# Block.net
KiCad netlist of a schematic drawn in Altium Designer
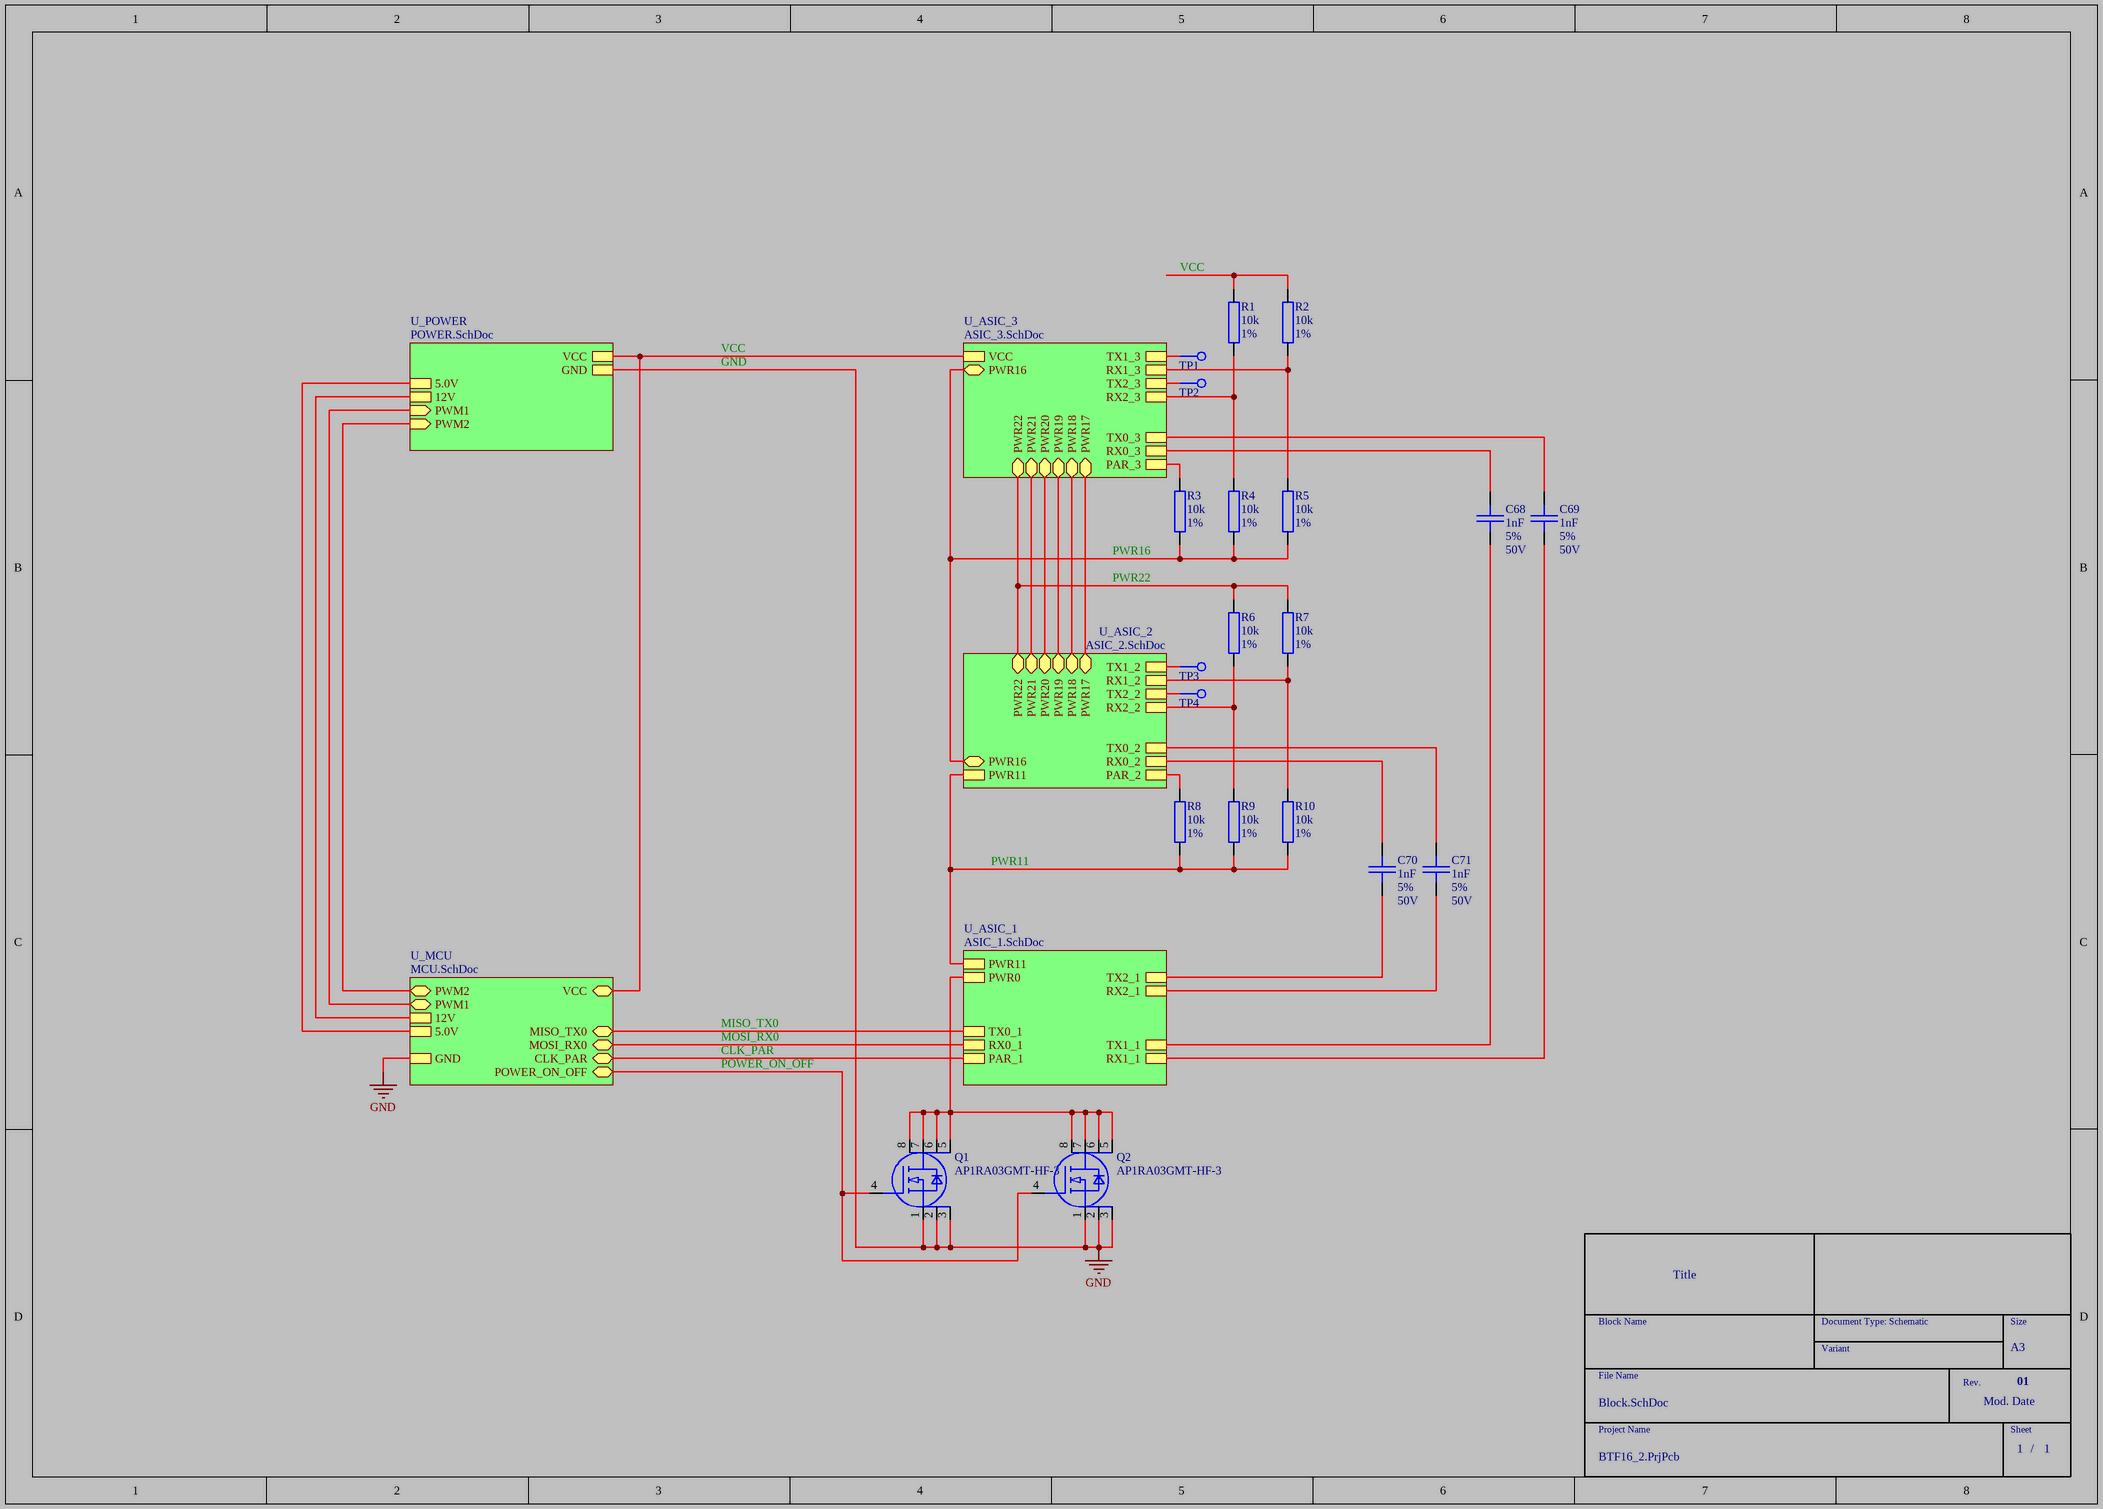
[diagram p0: Block.SchDoc]

(export (version "E")
  (design (tool "Eeschema 10.0.6"))
  (components
    (comp (ref "C68")
      (value "C")
      (footprint "SMD_0603_CAPC1608X95N")
      (fields
        (field (name "DB_PART_NUMBER") "CAP000020649")
        (field (name "DB_VALUE") "1nF")
        (field (name "DB_TOLERANCE") "5%")
        (field (name "DB_VOLTAGE") "50V")
        (field (name "DB_MANUFACTURER_PART") "KEMET    C0603F102J5RAC")
      )
      (libsource (lib "Database_Libs1") (part "C"))
    )
    (comp (ref "C69")
      (value "C")
      (footprint "SMD_0603_CAPC1608X95N")
      (fields
        (field (name "DB_PART_NUMBER") "CAP000020649")
        (field (name "DB_VALUE") "1nF")
        (field (name "DB_TOLERANCE") "5%")
        (field (name "DB_VOLTAGE") "50V")
        (field (name "DB_MANUFACTURER_PART") "KEMET    C0603F102J5RAC")
      )
      (libsource (lib "Database_Libs1") (part "C"))
    )
    (comp (ref "C70")
      (value "C")
      (footprint "SMD_0603_CAPC1608X95N")
      (fields
        (field (name "DB_PART_NUMBER") "CAP000020649")
        (field (name "DB_VALUE") "1nF")
        (field (name "DB_TOLERANCE") "5%")
        (field (name "DB_VOLTAGE") "50V")
        (field (name "DB_MANUFACTURER_PART") "KEMET    C0603F102J5RAC")
      )
      (libsource (lib "Database_Libs1") (part "C"))
    )
    (comp (ref "C71")
      (value "C")
      (footprint "SMD_0603_CAPC1608X95N")
      (fields
        (field (name "DB_PART_NUMBER") "CAP000020649")
        (field (name "DB_VALUE") "1nF")
        (field (name "DB_TOLERANCE") "5%")
        (field (name "DB_VOLTAGE") "50V")
        (field (name "DB_MANUFACTURER_PART") "KEMET    C0603F102J5RAC")
      )
      (libsource (lib "Database_Libs1") (part "C"))
    )
    (comp (ref "Q1")
      (value "MOS_N_D1_S1S2S3G4D5D6D7D8")
      (footprint "SMD_SOIC127P600X110-9AN")
      (fields
        (field (name "DB_PART_NUMBER") "TRA000001604")
        (field (name "DB_VALUE") "AP1RA03GMT-HF-3")
        (field (name "DB_MANUFACTURER_PART") "ADVANCED POWER ELECTRONICS CORP      AP1RA03GMT-HF-3")
        (field (name "DB_APPROVED_BY") "VSN")
      )
      (libsource (lib "Database_Libs1") (part "MOS_N_D1_S1S2S3G4D5D6D7D8"))
    )
    (comp (ref "Q2")
      (value "MOS_N_D1_S1S2S3G4D5D6D7D8")
      (footprint "SMD_SOIC127P600X110-9AN")
      (fields
        (field (name "DB_PART_NUMBER") "TRA000001604")
        (field (name "DB_VALUE") "AP1RA03GMT-HF-3")
        (field (name "DB_MANUFACTURER_PART") "ADVANCED POWER ELECTRONICS CORP      AP1RA03GMT-HF-3")
        (field (name "DB_APPROVED_BY") "VSN")
      )
      (libsource (lib "Database_Libs1") (part "MOS_N_D1_S1S2S3G4D5D6D7D8"))
    )
    (comp (ref "R1")
      (value "R")
      (footprint "SMD_0603_RESC1608X55N")
      (fields
        (field (name "DB_PART_NUMBER") "RES000008891")
        (field (name "DB_VALUE") "10k")
        (field (name "DB_TOLERANCE") "1%")
        (field (name "DB_MANUFACTURER_PART") "VISHAY    CRCW060310K0FKEA")
        (field (name "DB_APPROVED_BY") "VSN")
      )
      (libsource (lib "Database_Libs1") (part "R"))
    )
    (comp (ref "R2")
      (value "R")
      (footprint "SMD_0603_RESC1608X55N")
      (fields
        (field (name "DB_PART_NUMBER") "RES000008891")
        (field (name "DB_VALUE") "10k")
        (field (name "DB_TOLERANCE") "1%")
        (field (name "DB_MANUFACTURER_PART") "VISHAY    CRCW060310K0FKEA")
        (field (name "DB_APPROVED_BY") "VSN")
      )
      (libsource (lib "Database_Libs1") (part "R"))
    )
    (comp (ref "R3")
      (value "R")
      (footprint "SMD_0603_RESC1608X55N")
      (fields
        (field (name "DB_PART_NUMBER") "RES000008891")
        (field (name "DB_VALUE") "10k")
        (field (name "DB_TOLERANCE") "1%")
        (field (name "DB_MANUFACTURER_PART") "VISHAY    CRCW060310K0FKEA")
        (field (name "DB_APPROVED_BY") "VSN")
      )
      (libsource (lib "Database_Libs1") (part "R"))
    )
    (comp (ref "R4")
      (value "R")
      (footprint "SMD_0603_RESC1608X55N")
      (fields
        (field (name "DB_PART_NUMBER") "RES000008891")
        (field (name "DB_VALUE") "10k")
        (field (name "DB_TOLERANCE") "1%")
        (field (name "DB_MANUFACTURER_PART") "VISHAY    CRCW060310K0FKEA")
        (field (name "DB_APPROVED_BY") "VSN")
      )
      (libsource (lib "Database_Libs1") (part "R"))
    )
    (comp (ref "R5")
      (value "R")
      (footprint "SMD_0603_RESC1608X55N")
      (fields
        (field (name "DB_PART_NUMBER") "RES000008891")
        (field (name "DB_VALUE") "10k")
        (field (name "DB_TOLERANCE") "1%")
        (field (name "DB_MANUFACTURER_PART") "VISHAY    CRCW060310K0FKEA")
        (field (name "DB_APPROVED_BY") "VSN")
      )
      (libsource (lib "Database_Libs1") (part "R"))
    )
    (comp (ref "R6")
      (value "R")
      (footprint "SMD_0603_RESC1608X55N")
      (fields
        (field (name "DB_PART_NUMBER") "RES000008891")
        (field (name "DB_VALUE") "10k")
        (field (name "DB_TOLERANCE") "1%")
        (field (name "DB_MANUFACTURER_PART") "VISHAY    CRCW060310K0FKEA")
        (field (name "DB_APPROVED_BY") "VSN")
      )
      (libsource (lib "Database_Libs1") (part "R"))
    )
    (comp (ref "R7")
      (value "R")
      (footprint "SMD_0603_RESC1608X55N")
      (fields
        (field (name "DB_PART_NUMBER") "RES000008891")
        (field (name "DB_VALUE") "10k")
        (field (name "DB_TOLERANCE") "1%")
        (field (name "DB_MANUFACTURER_PART") "VISHAY    CRCW060310K0FKEA")
        (field (name "DB_APPROVED_BY") "VSN")
      )
      (libsource (lib "Database_Libs1") (part "R"))
    )
    (comp (ref "R8")
      (value "R")
      (footprint "SMD_0603_RESC1608X55N")
      (fields
        (field (name "DB_PART_NUMBER") "RES000008891")
        (field (name "DB_VALUE") "10k")
        (field (name "DB_TOLERANCE") "1%")
        (field (name "DB_MANUFACTURER_PART") "VISHAY    CRCW060310K0FKEA")
        (field (name "DB_APPROVED_BY") "VSN")
      )
      (libsource (lib "Database_Libs1") (part "R"))
    )
    (comp (ref "R9")
      (value "R")
      (footprint "SMD_0603_RESC1608X55N")
      (fields
        (field (name "DB_PART_NUMBER") "RES000008891")
        (field (name "DB_VALUE") "10k")
        (field (name "DB_TOLERANCE") "1%")
        (field (name "DB_MANUFACTURER_PART") "VISHAY    CRCW060310K0FKEA")
        (field (name "DB_APPROVED_BY") "VSN")
      )
      (libsource (lib "Database_Libs1") (part "R"))
    )
    (comp (ref "R10")
      (value "R")
      (footprint "SMD_0603_RESC1608X55N")
      (fields
        (field (name "DB_PART_NUMBER") "RES000008891")
        (field (name "DB_VALUE") "10k")
        (field (name "DB_TOLERANCE") "1%")
        (field (name "DB_MANUFACTURER_PART") "VISHAY    CRCW060310K0FKEA")
        (field (name "DB_APPROVED_BY") "VSN")
      )
      (libsource (lib "Database_Libs1") (part "R"))
    )
    (comp (ref "TP1")
      (value "TEST_POINT_1")
      (footprint "SMD_TP_100-254")
      (fields (field (name "DB_PART_NUMBER") "TPO000000001"))
      (libsource (lib "Database_Libs1") (part "TEST_POINT_1"))
    )
    (comp (ref "TP2")
      (value "TEST_POINT_1")
      (footprint "SMD_TP_100-254")
      (fields (field (name "DB_PART_NUMBER") "TPO000000001"))
      (libsource (lib "Database_Libs1") (part "TEST_POINT_1"))
    )
    (comp (ref "TP3")
      (value "TEST_POINT_1")
      (footprint "SMD_TP_100-254")
      (fields (field (name "DB_PART_NUMBER") "TPO000000001"))
      (libsource (lib "Database_Libs1") (part "TEST_POINT_1"))
    )
    (comp (ref "TP4")
      (value "TEST_POINT_1")
      (footprint "SMD_TP_100-254")
      (fields (field (name "DB_PART_NUMBER") "TPO000000001"))
      (libsource (lib "Database_Libs1") (part "TEST_POINT_1"))
    )
  )
  (nets
    (net (code "6") (name "/PAR_2") (class "Default")
      (node (ref "R8") (pin "1") (pinfunction "1_1") (pintype "passive"))
    )
    (net (code "7") (name "/PAR_3") (class "Default")
      (node (ref "R3") (pin "1") (pinfunction "1_1") (pintype "passive"))
    )
    (net (code "8") (name "/POWER_ON_OFF") (class "Default")
      (node (ref "Q1") (pin "4") (pinfunction "G_4") (pintype "passive"))
      (node (ref "Q2") (pin "4") (pinfunction "G_4") (pintype "passive"))
    )
    (net (code "11") (name "/PWR0") (class "Default")
      (node (ref "Q1") (pin "5") (pinfunction "D_5") (pintype "passive"))
      (node (ref "Q1") (pin "6") (pinfunction "D_6") (pintype "passive"))
      (node (ref "Q1") (pin "7") (pinfunction "D_7") (pintype "passive"))
      (node (ref "Q1") (pin "8") (pinfunction "D_8") (pintype "passive"))
      (node (ref "Q2") (pin "5") (pinfunction "D_5") (pintype "passive"))
      (node (ref "Q2") (pin "6") (pinfunction "D_6") (pintype "passive"))
      (node (ref "Q2") (pin "7") (pinfunction "D_7") (pintype "passive"))
      (node (ref "Q2") (pin "8") (pinfunction "D_8") (pintype "passive"))
    )
    (net (code "12") (name "/PWR11") (class "Default")
      (node (ref "R10") (pin "2") (pinfunction "2_2") (pintype "passive"))
      (node (ref "R8") (pin "2") (pinfunction "2_2") (pintype "passive"))
      (node (ref "R9") (pin "2") (pinfunction "2_2") (pintype "passive"))
    )
    (net (code "13") (name "/PWR16") (class "Default")
      (node (ref "R3") (pin "2") (pinfunction "2_2") (pintype "passive"))
      (node (ref "R4") (pin "2") (pinfunction "2_2") (pintype "passive"))
      (node (ref "R5") (pin "2") (pinfunction "2_2") (pintype "passive"))
    )
    (net (code "19") (name "/PWR22") (class "Default")
      (node (ref "R6") (pin "2") (pinfunction "2_2") (pintype "passive"))
      (node (ref "R7") (pin "2") (pinfunction "2_2") (pintype "passive"))
    )
    (net (code "20") (name "/RX0_2") (class "Default")
      (node (ref "C70") (pin "1") (pinfunction "1_1") (pintype "passive"))
    )
    (net (code "21") (name "/RX0_3") (class "Default")
      (node (ref "C68") (pin "1") (pinfunction "1_1") (pintype "passive"))
    )
    (net (code "22") (name "/RX1_1") (class "Default")
      (node (ref "C69") (pin "2") (pinfunction "2_2") (pintype "passive"))
    )
    (net (code "23") (name "/RX1_2") (class "Default")
      (node (ref "R10") (pin "1") (pinfunction "1_1") (pintype "passive"))
      (node (ref "R7") (pin "1") (pinfunction "1_1") (pintype "passive"))
    )
    (net (code "24") (name "/RX1_3") (class "Default")
      (node (ref "R2") (pin "1") (pinfunction "1_1") (pintype "passive"))
      (node (ref "R5") (pin "1") (pinfunction "1_1") (pintype "passive"))
    )
    (net (code "25") (name "/RX2_1") (class "Default")
      (node (ref "C71") (pin "2") (pinfunction "2_2") (pintype "passive"))
    )
    (net (code "26") (name "/RX2_2") (class "Default")
      (node (ref "R6") (pin "1") (pinfunction "1_1") (pintype "passive"))
      (node (ref "R9") (pin "1") (pinfunction "1_1") (pintype "passive"))
    )
    (net (code "27") (name "/RX2_3") (class "Default")
      (node (ref "R1") (pin "1") (pinfunction "1_1") (pintype "passive"))
      (node (ref "R4") (pin "1") (pinfunction "1_1") (pintype "passive"))
    )
    (net (code "28") (name "/TX0_2") (class "Default")
      (node (ref "C71") (pin "1") (pinfunction "1_1") (pintype "passive"))
    )
    (net (code "29") (name "/TX0_3") (class "Default")
      (node (ref "C69") (pin "1") (pinfunction "1_1") (pintype "passive"))
    )
    (net (code "30") (name "/TX1_1") (class "Default")
      (node (ref "C68") (pin "2") (pinfunction "2_2") (pintype "passive"))
    )
    (net (code "31") (name "/TX1_2") (class "Default")
      (node (ref "TP3") (pin "1") (pinfunction "1_1") (pintype "passive"))
    )
    (net (code "32") (name "/TX1_3") (class "Default")
      (node (ref "TP1") (pin "1") (pinfunction "1_1") (pintype "passive"))
    )
    (net (code "33") (name "/TX2_1") (class "Default")
      (node (ref "C70") (pin "2") (pinfunction "2_2") (pintype "passive"))
    )
    (net (code "34") (name "/TX2_2") (class "Default")
      (node (ref "TP4") (pin "1") (pinfunction "1_1") (pintype "passive"))
    )
    (net (code "35") (name "/TX2_3") (class "Default")
      (node (ref "TP2") (pin "1") (pinfunction "1_1") (pintype "passive"))
    )
    (net (code "36") (name "/VCC") (class "Default")
      (node (ref "R1") (pin "2") (pinfunction "2_2") (pintype "passive"))
      (node (ref "R2") (pin "2") (pinfunction "2_2") (pintype "passive"))
    )
    (net (code "37") (name "GND") (class "Default")
      (node (ref "Q1") (pin "1") (pinfunction "S_1") (pintype "passive"))
      (node (ref "Q1") (pin "2") (pinfunction "S_2") (pintype "passive"))
      (node (ref "Q1") (pin "3") (pinfunction "S_3") (pintype "passive"))
      (node (ref "Q2") (pin "1") (pinfunction "S_1") (pintype "passive"))
      (node (ref "Q2") (pin "2") (pinfunction "S_2") (pintype "passive"))
      (node (ref "Q2") (pin "3") (pinfunction "S_3") (pintype "passive"))
    )
  )
)
